# power_block.net
KiCad netlist of a schematic drawn in Altium Designer
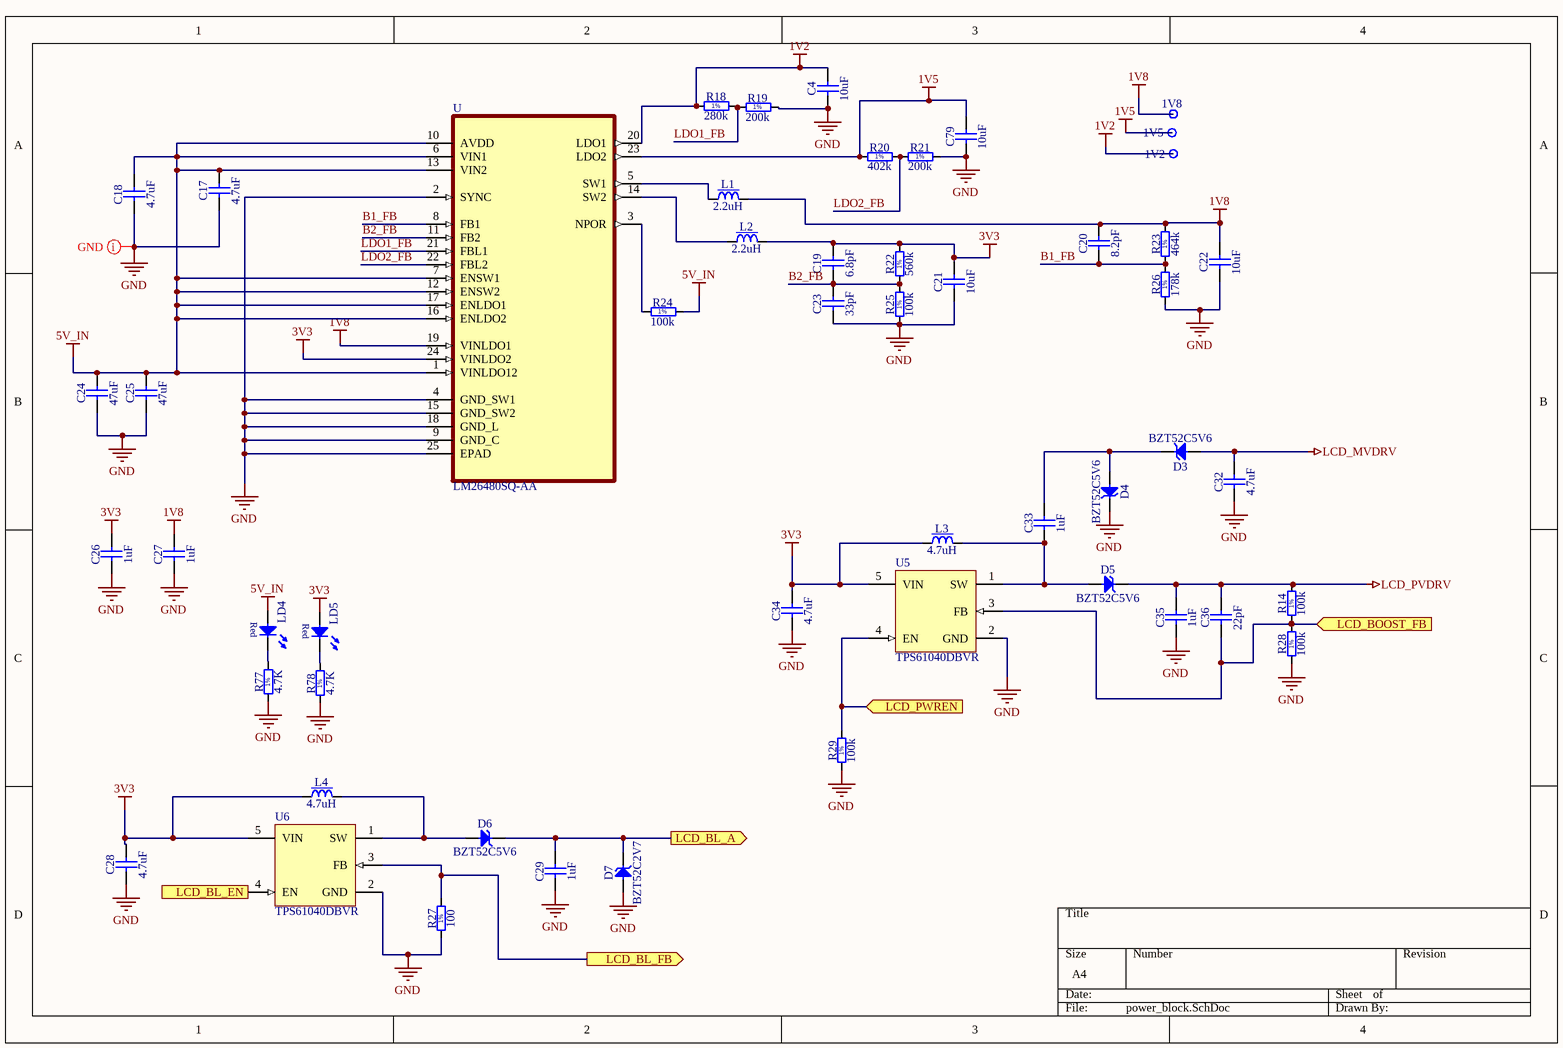
[diagram p0: power_block.SchDoc]

(export (version "E")
  (design (tool "Eeschema 10.0.6"))
  (components
    (comp (ref "1V2")
      (value "Test Point")
      (footprint "TPS127")
      (fields (field (name "PART NUMBER") "SMD_PAD_1.27X1.27MM") (field (name "AUTHOR") "CERN DEM JLC"))
      (libsource (lib "Eletro-mechanical") (part "Test Point"))
    )
    (comp (ref "1V5")
      (value "Test Point")
      (footprint "TPS127")
      (fields (field (name "PART NUMBER") "SMD_PAD_1.27X1.27MM") (field (name "AUTHOR") "CERN DEM JLC"))
      (libsource (lib "Eletro-mechanical") (part "Test Point"))
    )
    (comp (ref "1V8")
      (value "Test Point")
      (footprint "TPS127")
      (fields (field (name "PART NUMBER") "SMD_PAD_1.27X1.27MM") (field (name "AUTHOR") "CERN DEM JLC"))
      (libsource (lib "Eletro-mechanical") (part "Test Point"))
    )
    (comp (ref "C4")
      (value "10uF")
      (footprint "CAPC2013X100N")
      (description "Non-polarised capacitor")
      (fields
        (field (name "PART NUMBER") "CC0805_1.5NF_50V_5%_C0G")
        (field (name "VOLTAGE") "50V")
        (field (name "AUTHOR") "CERN DEM BC")
      )
      (libsource (lib "Capacitors") (part "Capacitor - non polarized"))
    )
    (comp (ref "C17")
      (value "4.7uF")
      (footprint "CAPC2013X100N")
      (description "Non-polarised capacitor")
      (fields
        (field (name "PART NUMBER") "CC0805_1.5NF_50V_5%_C0G")
        (field (name "VOLTAGE") "50V")
        (field (name "AUTHOR") "CERN DEM BC")
      )
      (libsource (lib "Capacitors") (part "Capacitor - non polarized"))
    )
    (comp (ref "C18")
      (value "4.7uF")
      (footprint "CAPC2013X100N")
      (description "Non-polarised capacitor")
      (fields
        (field (name "PART NUMBER") "CC0805_1.5NF_50V_5%_C0G")
        (field (name "VOLTAGE") "50V")
        (field (name "AUTHOR") "CERN DEM BC")
      )
      (libsource (lib "Capacitors") (part "Capacitor - non polarized"))
    )
    (comp (ref "C19")
      (value "6.8pF")
      (footprint "CAPC2013X100N")
      (description "Non-polarised capacitor")
      (fields
        (field (name "PART NUMBER") "CC0805_1.5NF_50V_5%_C0G")
        (field (name "VOLTAGE") "50V")
        (field (name "AUTHOR") "CERN DEM BC")
      )
      (libsource (lib "Capacitors") (part "Capacitor - non polarized"))
    )
    (comp (ref "C20")
      (value "8.2pF")
      (footprint "CAPC2013X100N")
      (description "Non-polarised capacitor")
      (fields
        (field (name "PART NUMBER") "CC0805_1.5NF_50V_5%_C0G")
        (field (name "VOLTAGE") "50V")
        (field (name "AUTHOR") "CERN DEM BC")
      )
      (libsource (lib "Capacitors") (part "Capacitor - non polarized"))
    )
    (comp (ref "C21")
      (value "10uF")
      (footprint "CAPC2013X100N")
      (description "Non-polarised capacitor")
      (fields
        (field (name "PART NUMBER") "CC0805_1.5NF_50V_5%_C0G")
        (field (name "VOLTAGE") "50V")
        (field (name "AUTHOR") "CERN DEM BC")
      )
      (libsource (lib "Capacitors") (part "Capacitor - non polarized"))
    )
    (comp (ref "C22")
      (value "10uF")
      (footprint "CAPC2013X100N")
      (description "Non-polarised capacitor")
      (fields
        (field (name "PART NUMBER") "CC0805_1.5NF_50V_5%_C0G")
        (field (name "VOLTAGE") "50V")
        (field (name "AUTHOR") "CERN DEM BC")
      )
      (libsource (lib "Capacitors") (part "Capacitor - non polarized"))
    )
    (comp (ref "C23")
      (value "33pF")
      (footprint "CAPC2013X100N")
      (description "Non-polarised capacitor")
      (fields
        (field (name "PART NUMBER") "CC0805_1.5NF_50V_5%_C0G")
        (field (name "VOLTAGE") "50V")
        (field (name "AUTHOR") "CERN DEM BC")
      )
      (libsource (lib "Capacitors") (part "Capacitor - non polarized"))
    )
    (comp (ref "C24")
      (value "47uF")
      (footprint "CAPC2013X100N")
      (description "Non-polarised capacitor")
      (fields
        (field (name "PART NUMBER") "CC0805_1.5NF_50V_5%_C0G")
        (field (name "VOLTAGE") "50V")
        (field (name "AUTHOR") "CERN DEM BC")
      )
      (libsource (lib "Capacitors") (part "Capacitor - non polarized"))
    )
    (comp (ref "C25")
      (value "47uF")
      (footprint "CAPC2013X100N")
      (description "Non-polarised capacitor")
      (fields
        (field (name "PART NUMBER") "CC0805_1.5NF_50V_5%_C0G")
        (field (name "VOLTAGE") "50V")
        (field (name "AUTHOR") "CERN DEM BC")
      )
      (libsource (lib "Capacitors") (part "Capacitor - non polarized"))
    )
    (comp (ref "C26")
      (value "1uF")
      (footprint "CAPC2013X100N")
      (description "Non-polarised capacitor")
      (fields
        (field (name "PART NUMBER") "CC0805_1.5NF_50V_5%_C0G")
        (field (name "VOLTAGE") "50V")
        (field (name "AUTHOR") "CERN DEM BC")
      )
      (libsource (lib "Capacitors") (part "Capacitor - non polarized"))
    )
    (comp (ref "C27")
      (value "1uF")
      (footprint "CAPC2013X100N")
      (description "Non-polarised capacitor")
      (fields
        (field (name "PART NUMBER") "CC0805_1.5NF_50V_5%_C0G")
        (field (name "VOLTAGE") "50V")
        (field (name "AUTHOR") "CERN DEM BC")
      )
      (libsource (lib "Capacitors") (part "Capacitor - non polarized"))
    )
    (comp (ref "C28")
      (value "4.7uF")
      (footprint "CAPC2013X100N")
      (description "Non-polarised capacitor")
      (fields
        (field (name "PART NUMBER") "CC0805_1.5NF_50V_5%_C0G")
        (field (name "VOLTAGE") "50V")
        (field (name "AUTHOR") "CERN DEM BC")
      )
      (libsource (lib "Capacitors") (part "Capacitor - non polarized"))
    )
    (comp (ref "C29")
      (value "1uF")
      (footprint "CAPC2013X100N")
      (description "Non-polarised capacitor")
      (fields
        (field (name "PART NUMBER") "CC0805_1.5NF_50V_5%_C0G")
        (field (name "VOLTAGE") "50V")
        (field (name "AUTHOR") "CERN DEM BC")
      )
      (libsource (lib "Capacitors") (part "Capacitor - non polarized"))
    )
    (comp (ref "C32")
      (value "4.7uF")
      (footprint "CAPC2013X100N")
      (description "Non-polarised capacitor")
      (fields
        (field (name "PART NUMBER") "CC0805_1.5NF_50V_5%_C0G")
        (field (name "VOLTAGE") "50V")
        (field (name "AUTHOR") "CERN DEM BC")
      )
      (libsource (lib "Capacitors") (part "Capacitor - non polarized"))
    )
    (comp (ref "C33")
      (value "1uF")
      (footprint "CAPC2013X100N")
      (description "Non-polarised capacitor")
      (fields
        (field (name "PART NUMBER") "CC0805_1.5NF_50V_5%_C0G")
        (field (name "VOLTAGE") "50V")
        (field (name "AUTHOR") "CERN DEM BC")
      )
      (libsource (lib "Capacitors") (part "Capacitor - non polarized"))
    )
    (comp (ref "C34")
      (value "4.7uF")
      (footprint "CAPC2013X100N")
      (description "Non-polarised capacitor")
      (fields
        (field (name "PART NUMBER") "CC0805_1.5NF_50V_5%_C0G")
        (field (name "VOLTAGE") "50V")
        (field (name "AUTHOR") "CERN DEM BC")
      )
      (libsource (lib "Capacitors") (part "Capacitor - non polarized"))
    )
    (comp (ref "C35")
      (value "1uF")
      (footprint "CAPC2013X100N")
      (description "Non-polarised capacitor")
      (fields
        (field (name "PART NUMBER") "CC0805_1.5NF_50V_5%_C0G")
        (field (name "VOLTAGE") "50V")
        (field (name "AUTHOR") "CERN DEM BC")
      )
      (libsource (lib "Capacitors") (part "Capacitor - non polarized"))
    )
    (comp (ref "C36")
      (value "22pF")
      (footprint "CAPC2013X100N")
      (description "Non-polarised capacitor")
      (fields
        (field (name "PART NUMBER") "CC0805_1.5NF_50V_5%_C0G")
        (field (name "VOLTAGE") "50V")
        (field (name "AUTHOR") "CERN DEM BC")
      )
      (libsource (lib "Capacitors") (part "Capacitor - non polarized"))
    )
    (comp (ref "C79")
      (value "10uF")
      (footprint "CAPC2013X100N")
      (description "Non-polarised capacitor")
      (fields
        (field (name "PART NUMBER") "CC0805_1.5NF_50V_5%_C0G")
        (field (name "VOLTAGE") "50V")
        (field (name "AUTHOR") "CERN DEM BC")
      )
      (libsource (lib "Capacitors") (part "Capacitor - non polarized"))
    )
    (comp (ref "D3")
      (value "BZT52C5V6")
      (footprint "SOD3715X145N")
      (description "Zener Diode")
      (fields
        (field (name "VOLTAGE") "5V6")
        (field (name "POWER") "0.5W")
        (field (name "AUTHOR") "CERN DEM JLC")
      )
      (libsource (lib "ICs And Semiconductors") (part "Diode Zener"))
    )
    (comp (ref "D4")
      (value "BZT52C5V6")
      (footprint "SOD3715X145N")
      (description "Zener Diode")
      (fields
        (field (name "VOLTAGE") "5V6")
        (field (name "POWER") "0.5W")
        (field (name "AUTHOR") "CERN DEM JLC")
      )
      (libsource (lib "ICs And Semiconductors") (part "Diode Zener"))
    )
    (comp (ref "D5")
      (value "BZT52C5V6")
      (footprint "SOD3715X145N")
      (description "Zener Diode")
      (fields
        (field (name "VOLTAGE") "5V6")
        (field (name "POWER") "0.5W")
        (field (name "AUTHOR") "CERN DEM JLC")
      )
      (libsource (lib "ICs And Semiconductors") (part "Diode Zener"))
    )
    (comp (ref "D6")
      (value "BZT52C5V6")
      (footprint "SOD3715X145N")
      (description "Zener Diode")
      (fields
        (field (name "VOLTAGE") "5V6")
        (field (name "POWER") "0.5W")
        (field (name "AUTHOR") "CERN DEM JLC")
      )
      (libsource (lib "ICs And Semiconductors") (part "Diode Zener"))
    )
    (comp (ref "D7")
      (value "BZT52C2V7")
      (footprint "SOD3715X145N")
      (description "Zener Diode")
      (fields
        (field (name "VOLTAGE") "2V7")
        (field (name "POWER") "500mW")
        (field (name "AUTHOR") "CERN DEM JLC")
      )
      (libsource (lib "ICs And Semiconductors") (part "Diode Zener"))
    )
    (comp (ref "L1")
      (value "2.2uH")
      (footprint "IND_MURATA-PS_8200")
      (description "Inductor With Core")
      (fields
        (field (name "PART NUMBER") "IND_22UH_10%_MURATA-PS_8200")
        (field (name "POWER") "320mA")
        (field (name "AUTHOR") "CERN DEM JMW")
      )
      (libsource (lib "Inductors & Transformers") (part "Inductor With Magnetic core"))
    )
    (comp (ref "L2")
      (value "2.2uH")
      (footprint "IND_MURATA-PS_8200")
      (description "Inductor With Core")
      (fields
        (field (name "PART NUMBER") "IND_22UH_10%_MURATA-PS_8200")
        (field (name "POWER") "320mA")
        (field (name "AUTHOR") "CERN DEM JMW")
      )
      (libsource (lib "Inductors & Transformers") (part "Inductor With Magnetic core"))
    )
    (comp (ref "L3")
      (value "4.7uH")
      (footprint "IND_MURATA-PS_8200")
      (description "Inductor With Core")
      (fields
        (field (name "PART NUMBER") "IND_22UH_10%_MURATA-PS_8200")
        (field (name "POWER") "320mA")
        (field (name "AUTHOR") "CERN DEM JMW")
      )
      (libsource (lib "Inductors & Transformers") (part "Inductor With Magnetic core"))
    )
    (comp (ref "L4")
      (value "4.7uH")
      (footprint "IND_MURATA-PS_8200")
      (description "Inductor With Core")
      (fields
        (field (name "PART NUMBER") "IND_22UH_10%_MURATA-PS_8200")
        (field (name "POWER") "320mA")
        (field (name "AUTHOR") "CERN DEM JMW")
      )
      (libsource (lib "Inductors & Transformers") (part "Inductor With Magnetic core"))
    )
    (comp (ref "LD4")
      (value "Super Red")
      (footprint "LED_OSRAM_LSR976")
      (description "LED Red 1C 2A")
      (fields
        (field (name "PART NUMBER") "LED_OSRAM_LSR976")
        (field (name "MANUFACTURER") "OSRAM")
        (field (name "AUTHOR") "CERN DEM JLC")
      )
      (libsource (lib "ICs And Semiconductors") (part "LED Red 1C 2A"))
    )
    (comp (ref "LD5")
      (value "Super Red")
      (footprint "LED_OSRAM_LSR976")
      (description "LED Red 1C 2A")
      (fields
        (field (name "PART NUMBER") "LED_OSRAM_LSR976")
        (field (name "MANUFACTURER") "OSRAM")
        (field (name "AUTHOR") "CERN DEM JLC")
      )
      (libsource (lib "ICs And Semiconductors") (part "LED Red 1C 2A"))
    )
    (comp (ref "R14")
      (value "100k")
      (footprint "RESC1608X55N")
      (description "Resistor - 1%")
      (fields
        (field (name "PART NUMBER") "R0603_100K_1%_0.1W_100PPM")
        (field (name "POWER") "0.1W")
        (field (name "AUTHOR") "CERN DEM JLC")
      )
      (libsource (lib "Resistors") (part "Resistor - 1%"))
    )
    (comp (ref "R18")
      (value "280k")
      (footprint "RESC1608X55N")
      (description "Resistor - 1%")
      (fields
        (field (name "PART NUMBER") "R0603_100K_1%_0.1W_100PPM")
        (field (name "POWER") "0.1W")
        (field (name "AUTHOR") "CERN DEM JLC")
      )
      (libsource (lib "Resistors") (part "Resistor - 1%"))
    )
    (comp (ref "R19")
      (value "200k")
      (footprint "RESC1608X55N")
      (description "Resistor - 1%")
      (fields
        (field (name "PART NUMBER") "R0603_100K_1%_0.1W_100PPM")
        (field (name "POWER") "0.1W")
        (field (name "AUTHOR") "CERN DEM JLC")
      )
      (libsource (lib "Resistors") (part "Resistor - 1%"))
    )
    (comp (ref "R20")
      (value "402k")
      (footprint "RESC1608X55N")
      (description "Resistor - 1%")
      (fields
        (field (name "PART NUMBER") "R0603_100K_1%_0.1W_100PPM")
        (field (name "POWER") "0.1W")
        (field (name "AUTHOR") "CERN DEM JLC")
      )
      (libsource (lib "Resistors") (part "Resistor - 1%"))
    )
    (comp (ref "R21")
      (value "200k")
      (footprint "RESC1608X55N")
      (description "Resistor - 1%")
      (fields
        (field (name "PART NUMBER") "R0603_100K_1%_0.1W_100PPM")
        (field (name "POWER") "0.1W")
        (field (name "AUTHOR") "CERN DEM JLC")
      )
      (libsource (lib "Resistors") (part "Resistor - 1%"))
    )
    (comp (ref "R22")
      (value "560k")
      (footprint "RESC1608X55N")
      (description "Resistor - 1%")
      (fields
        (field (name "PART NUMBER") "R0603_100K_1%_0.1W_100PPM")
        (field (name "POWER") "0.1W")
        (field (name "AUTHOR") "CERN DEM JLC")
      )
      (libsource (lib "Resistors") (part "Resistor - 1%"))
    )
    (comp (ref "R23")
      (value "464k")
      (footprint "RESC1608X55N")
      (description "Resistor - 1%")
      (fields
        (field (name "PART NUMBER") "R0603_100K_1%_0.1W_100PPM")
        (field (name "POWER") "0.1W")
        (field (name "AUTHOR") "CERN DEM JLC")
      )
      (libsource (lib "Resistors") (part "Resistor - 1%"))
    )
    (comp (ref "R24")
      (value "100k")
      (footprint "RESC1608X55N")
      (description "Resistor - 1%")
      (fields
        (field (name "PART NUMBER") "R0603_100K_1%_0.1W_100PPM")
        (field (name "POWER") "0.1W")
        (field (name "AUTHOR") "CERN DEM JLC")
      )
      (libsource (lib "Resistors") (part "Resistor - 1%"))
    )
    (comp (ref "R25")
      (value "100k")
      (footprint "RESC1608X55N")
      (description "Resistor - 1%")
      (fields
        (field (name "PART NUMBER") "R0603_100K_1%_0.1W_100PPM")
        (field (name "POWER") "0.1W")
        (field (name "AUTHOR") "CERN DEM JLC")
      )
      (libsource (lib "Resistors") (part "Resistor - 1%"))
    )
    (comp (ref "R26")
      (value "178k")
      (footprint "RESC1608X55N")
      (description "Resistor - 1%")
      (fields
        (field (name "PART NUMBER") "R0603_100K_1%_0.1W_100PPM")
        (field (name "POWER") "0.1W")
        (field (name "AUTHOR") "CERN DEM JLC")
      )
      (libsource (lib "Resistors") (part "Resistor - 1%"))
    )
    (comp (ref "R27")
      (value "100")
      (footprint "RESC1608X55N")
      (description "Resistor - 1%")
      (fields
        (field (name "PART NUMBER") "R0603_100K_1%_0.1W_100PPM")
        (field (name "POWER") "0.1W")
        (field (name "AUTHOR") "CERN DEM JLC")
      )
      (libsource (lib "Resistors") (part "Resistor - 1%"))
    )
    (comp (ref "R28")
      (value "100k")
      (footprint "RESC1608X55N")
      (description "Resistor - 1%")
      (fields
        (field (name "PART NUMBER") "R0603_100K_1%_0.1W_100PPM")
        (field (name "POWER") "0.1W")
        (field (name "AUTHOR") "CERN DEM JLC")
      )
      (libsource (lib "Resistors") (part "Resistor - 1%"))
    )
    (comp (ref "R29")
      (value "100k")
      (footprint "RESC1608X55N")
      (description "Resistor - 1%")
      (fields
        (field (name "PART NUMBER") "R0603_100K_1%_0.1W_100PPM")
        (field (name "POWER") "0.1W")
        (field (name "AUTHOR") "CERN DEM JLC")
      )
      (libsource (lib "Resistors") (part "Resistor - 1%"))
    )
    (comp (ref "R77")
      (value "4.7K")
      (footprint "RESC1608X55N")
      (description "Resistor - 1%")
      (fields
        (field (name "PART NUMBER") "R0603_100K_1%_0.1W_100PPM")
        (field (name "POWER") "0.1W")
        (field (name "AUTHOR") "CERN DEM JLC")
      )
      (libsource (lib "Resistors") (part "Resistor - 1%"))
    )
    (comp (ref "R78")
      (value "4.7K")
      (footprint "RESC1608X55N")
      (description "Resistor - 1%")
      (fields
        (field (name "PART NUMBER") "R0603_100K_1%_0.1W_100PPM")
        (field (name "POWER") "0.1W")
        (field (name "AUTHOR") "CERN DEM JLC")
      )
      (libsource (lib "Resistors") (part "Resistor - 1%"))
    )
    (comp (ref "U")
      (value "LM26480SQ-AA")
      (footprint "QFN400X400X80-25N")
      (fields (field (name "MF") "Texas Instruments"))
      (libsource (lib "LM26480SQ-AA") (part "LM26480SQ-AA"))
    )
    (comp (ref "U5")
      (value "TPS61040DBVR")
      (footprint "TI-DBV5_L")
      (fields (field (name "MANUFACTURER") "Texas Instruments"))
      (libsource (lib "TI Power Management Lighting and Display") (part "TPS61040DBVR"))
    )
    (comp (ref "U6")
      (value "TPS61040DBVR")
      (footprint "TI-DBV5_L")
      (fields (field (name "MANUFACTURER") "Texas Instruments"))
      (libsource (lib "TI Power Management Lighting and Display") (part "TPS61040DBVR"))
    )
  )
  (nets
    (net (code "1") (name "/B1_FB") (class "Default")
      (node (ref "C20") (pin "1") (pinfunction "1_1") (pintype "passive"))
      (node (ref "R23") (pin "1") (pinfunction "1_1") (pintype "passive"))
      (node (ref "R26") (pin "2") (pinfunction "2_2") (pintype "passive"))
      (node (ref "U") (pin "8") (pinfunction "FB1_8") (pintype "input"))
    )
    (net (code "2") (name "/B2_FB") (class "Default")
      (node (ref "C19") (pin "1") (pinfunction "1_1") (pintype "passive"))
      (node (ref "C23") (pin "2") (pinfunction "2_2") (pintype "passive"))
      (node (ref "R22") (pin "1") (pinfunction "1_1") (pintype "passive"))
      (node (ref "R25") (pin "2") (pinfunction "2_2") (pintype "passive"))
      (node (ref "U") (pin "11") (pinfunction "FB2_11") (pintype "input"))
    )
    (net (code "3") (name "/LCD_BL_A") (class "Default")
      (node (ref "C29") (pin "2") (pinfunction "2_2") (pintype "passive"))
      (node (ref "D6") (pin "1") (pinfunction "C_1") (pintype "passive"))
      (node (ref "D7") (pin "1") (pinfunction "C_1") (pintype "passive"))
    )
    (net (code "4") (name "/LCD_BL_EN") (class "Default")
      (node (ref "U6") (pin "4") (pinfunction "EN_4") (pintype "input"))
    )
    (net (code "5") (name "/LCD_BL_FB") (class "Default")
      (node (ref "R27") (pin "2") (pinfunction "2_2") (pintype "passive"))
      (node (ref "U6") (pin "3") (pinfunction "FB_3") (pintype "input"))
    )
    (net (code "6") (name "/LCD_BOOST_FB") (class "Default")
      (node (ref "C36") (pin "1") (pinfunction "1_1") (pintype "passive"))
      (node (ref "R14") (pin "1") (pinfunction "1_1") (pintype "passive"))
      (node (ref "R28") (pin "2") (pinfunction "2_2") (pintype "passive"))
      (node (ref "U5") (pin "3") (pinfunction "FB_3") (pintype "input"))
    )
    (net (code "7") (name "/LCD_PWREN") (class "Default")
      (node (ref "R29") (pin "2") (pinfunction "2_2") (pintype "passive"))
      (node (ref "U5") (pin "4") (pinfunction "EN_4") (pintype "input"))
    )
    (net (code "8") (name "/LDO1_FB") (class "Default")
      (node (ref "R18") (pin "2") (pinfunction "2_2") (pintype "passive"))
      (node (ref "R19") (pin "1") (pinfunction "1_1") (pintype "passive"))
      (node (ref "U") (pin "21") (pinfunction "FBL1_21") (pintype "input"))
    )
    (net (code "9") (name "/LDO2_FB") (class "Default")
      (node (ref "R20") (pin "2") (pinfunction "2_2") (pintype "passive"))
      (node (ref "R21") (pin "1") (pinfunction "1_1") (pintype "passive"))
      (node (ref "U") (pin "22") (pinfunction "FBL2_22") (pintype "input"))
    )
    (net (code "10") (name "1V2") (class "Default")
      (node (ref "1V2") (pin "1") (pinfunction "1_1") (pintype "bidirectional"))
      (node (ref "C4") (pin "2") (pinfunction "2_2") (pintype "passive"))
      (node (ref "R18") (pin "1") (pinfunction "1_1") (pintype "passive"))
      (node (ref "U") (pin "20") (pinfunction "LDO1_20") (pintype "output"))
    )
    (net (code "11") (name "1V5") (class "Default")
      (node (ref "1V5") (pin "1") (pinfunction "1_1") (pintype "bidirectional"))
      (node (ref "C79") (pin "2") (pinfunction "2_2") (pintype "passive"))
      (node (ref "R20") (pin "1") (pinfunction "1_1") (pintype "passive"))
      (node (ref "U") (pin "23") (pinfunction "LDO2_23") (pintype "output"))
    )
    (net (code "12") (name "1V8") (class "Default")
      (node (ref "1V8") (pin "1") (pinfunction "1_1") (pintype "bidirectional"))
      (node (ref "C20") (pin "2") (pinfunction "2_2") (pintype "passive"))
      (node (ref "C22") (pin "2") (pinfunction "2_2") (pintype "passive"))
      (node (ref "C27") (pin "2") (pinfunction "2_2") (pintype "passive"))
      (node (ref "L1") (pin "2") (pinfunction "2_2") (pintype "passive"))
      (node (ref "R23") (pin "2") (pinfunction "2_2") (pintype "passive"))
      (node (ref "U") (pin "19") (pinfunction "VINLDO1_19") (pintype "input"))
    )
    (net (code "13") (name "3V3") (class "Default")
      (node (ref "C19") (pin "2") (pinfunction "2_2") (pintype "passive"))
      (node (ref "C21") (pin "2") (pinfunction "2_2") (pintype "passive"))
      (node (ref "C26") (pin "2") (pinfunction "2_2") (pintype "passive"))
      (node (ref "C28") (pin "2") (pinfunction "2_2") (pintype "passive"))
      (node (ref "C34") (pin "2") (pinfunction "2_2") (pintype "passive"))
      (node (ref "L2") (pin "2") (pinfunction "2_2") (pintype "passive"))
      (node (ref "L3") (pin "1") (pinfunction "1_1") (pintype "passive"))
      (node (ref "L4") (pin "1") (pinfunction "1_1") (pintype "passive"))
      (node (ref "LD5") (pin "2") (pinfunction "A_2") (pintype "passive"))
      (node (ref "R22") (pin "2") (pinfunction "2_2") (pintype "passive"))
      (node (ref "U") (pin "24") (pinfunction "VINLDO2_24") (pintype "input"))
      (node (ref "U5") (pin "5") (pinfunction "VIN_5") (pintype "power_in"))
      (node (ref "U6") (pin "5") (pinfunction "VIN_5") (pintype "power_in"))
    )
    (net (code "14") (name "5V_IN") (class "Default")
      (node (ref "C17") (pin "2") (pinfunction "2_2") (pintype "passive"))
      (node (ref "C18") (pin "2") (pinfunction "2_2") (pintype "passive"))
      (node (ref "C24") (pin "2") (pinfunction "2_2") (pintype "passive"))
      (node (ref "C25") (pin "2") (pinfunction "2_2") (pintype "passive"))
      (node (ref "LD4") (pin "2") (pinfunction "A_2") (pintype "passive"))
      (node (ref "R24") (pin "2") (pinfunction "2_2") (pintype "passive"))
      (node (ref "U") (pin "1") (pinfunction "VINLDO12_1") (pintype "input"))
      (node (ref "U") (pin "10") (pinfunction "AVDD_10") (pintype "power_in"))
      (node (ref "U") (pin "12") (pinfunction "ENSW2_12") (pintype "input"))
      (node (ref "U") (pin "13") (pinfunction "VIN2_13") (pintype "power_in"))
      (node (ref "U") (pin "16") (pinfunction "ENLDO2_16") (pintype "input"))
      (node (ref "U") (pin "17") (pinfunction "ENLDO1_17") (pintype "input"))
      (node (ref "U") (pin "6") (pinfunction "VIN1_6") (pintype "power_in"))
      (node (ref "U") (pin "7") (pinfunction "ENSW1_7") (pintype "input"))
    )
    (net (code "15") (name "GND") (class "Default")
      (node (ref "C17") (pin "1") (pinfunction "1_1") (pintype "passive"))
      (node (ref "C18") (pin "1") (pinfunction "1_1") (pintype "passive"))
      (node (ref "C21") (pin "1") (pinfunction "1_1") (pintype "passive"))
      (node (ref "C22") (pin "1") (pinfunction "1_1") (pintype "passive"))
      (node (ref "C23") (pin "1") (pinfunction "1_1") (pintype "passive"))
      (node (ref "C24") (pin "1") (pinfunction "1_1") (pintype "passive"))
      (node (ref "C25") (pin "1") (pinfunction "1_1") (pintype "passive"))
      (node (ref "C26") (pin "1") (pinfunction "1_1") (pintype "passive"))
      (node (ref "C27") (pin "1") (pinfunction "1_1") (pintype "passive"))
      (node (ref "C28") (pin "1") (pinfunction "1_1") (pintype "passive"))
      (node (ref "C29") (pin "1") (pinfunction "1_1") (pintype "passive"))
      (node (ref "C32") (pin "1") (pinfunction "1_1") (pintype "passive"))
      (node (ref "C34") (pin "1") (pinfunction "1_1") (pintype "passive"))
      (node (ref "C35") (pin "1") (pinfunction "1_1") (pintype "passive"))
      (node (ref "C4") (pin "1") (pinfunction "1_1") (pintype "passive"))
      (node (ref "C79") (pin "1") (pinfunction "1_1") (pintype "passive"))
      (node (ref "D4") (pin "1") (pinfunction "C_1") (pintype "passive"))
      (node (ref "D7") (pin "2") (pinfunction "A_2") (pintype "passive"))
      (node (ref "R19") (pin "2") (pinfunction "2_2") (pintype "passive"))
      (node (ref "R21") (pin "2") (pinfunction "2_2") (pintype "passive"))
      (node (ref "R25") (pin "1") (pinfunction "1_1") (pintype "passive"))
      (node (ref "R26") (pin "1") (pinfunction "1_1") (pintype "passive"))
      (node (ref "R27") (pin "1") (pinfunction "1_1") (pintype "passive"))
      (node (ref "R28") (pin "1") (pinfunction "1_1") (pintype "passive"))
      (node (ref "R29") (pin "1") (pinfunction "1_1") (pintype "passive"))
      (node (ref "R77") (pin "1") (pinfunction "1_1") (pintype "passive"))
      (node (ref "R78") (pin "1") (pinfunction "1_1") (pintype "passive"))
      (node (ref "U") (pin "15") (pinfunction "GND_SW2_15") (pintype "passive"))
      (node (ref "U") (pin "18") (pinfunction "GND_L_18") (pintype "passive"))
      (node (ref "U") (pin "2") (pinfunction "SYNC_2") (pintype "input"))
      (node (ref "U") (pin "25") (pinfunction "EPAD_25") (pintype "passive"))
      (node (ref "U") (pin "4") (pinfunction "GND_SW1_4") (pintype "passive"))
      (node (ref "U") (pin "9") (pinfunction "GND_C_9") (pintype "passive"))
      (node (ref "U5") (pin "2") (pinfunction "GND_2") (pintype "power_in"))
      (node (ref "U6") (pin "2") (pinfunction "GND_2") (pintype "power_in"))
    )
    (net (code "16") (name "LCD_MVDRV") (class "Default")
      (node (ref "C32") (pin "2") (pinfunction "2_2") (pintype "passive"))
      (node (ref "D3") (pin "2") (pinfunction "A_2") (pintype "passive"))
    )
    (net (code "17") (name "LCD_PVDRV") (class "Default")
      (node (ref "C35") (pin "2") (pinfunction "2_2") (pintype "passive"))
      (node (ref "C36") (pin "2") (pinfunction "2_2") (pintype "passive"))
      (node (ref "D5") (pin "1") (pinfunction "C_1") (pintype "passive"))
      (node (ref "R14") (pin "2") (pinfunction "2_2") (pintype "passive"))
    )
    (net (code "18") (name "Net-(D3-C)") (class "Default")
      (node (ref "C33") (pin "2") (pinfunction "2_2") (pintype "passive"))
      (node (ref "D3") (pin "1") (pinfunction "C_1") (pintype "passive"))
      (node (ref "D4") (pin "2") (pinfunction "A_2") (pintype "passive"))
    )
    (net (code "19") (name "Net-(D5-A)") (class "Default")
      (node (ref "C33") (pin "1") (pinfunction "1_1") (pintype "passive"))
      (node (ref "D5") (pin "2") (pinfunction "A_2") (pintype "passive"))
      (node (ref "L3") (pin "2") (pinfunction "2_2") (pintype "passive"))
      (node (ref "U5") (pin "1") (pinfunction "SW_1") (pintype "power_in"))
    )
    (net (code "20") (name "Net-(D6-A)") (class "Default")
      (node (ref "D6") (pin "2") (pinfunction "A_2") (pintype "passive"))
      (node (ref "L4") (pin "2") (pinfunction "2_2") (pintype "passive"))
      (node (ref "U6") (pin "1") (pinfunction "SW_1") (pintype "power_in"))
    )
    (net (code "21") (name "Net-(LD4-C)") (class "Default")
      (node (ref "LD4") (pin "1") (pinfunction "C_1") (pintype "passive"))
      (node (ref "R77") (pin "2") (pinfunction "2_2") (pintype "passive"))
    )
    (net (code "22") (name "Net-(LD5-C)") (class "Default")
      (node (ref "LD5") (pin "1") (pinfunction "C_1") (pintype "passive"))
      (node (ref "R78") (pin "2") (pinfunction "2_2") (pintype "passive"))
    )
    (net (code "23") (name "Net-(U-NPOR)") (class "Default")
      (node (ref "R24") (pin "1") (pinfunction "1_1") (pintype "passive"))
      (node (ref "U") (pin "3") (pinfunction "NPOR_3") (pintype "output"))
    )
    (net (code "24") (name "Net-(U-SW1)") (class "Default")
      (node (ref "L1") (pin "1") (pinfunction "1_1") (pintype "passive"))
      (node (ref "U") (pin "5") (pinfunction "SW1_5") (pintype "output"))
    )
    (net (code "25") (name "Net-(U-SW2)") (class "Default")
      (node (ref "L2") (pin "1") (pinfunction "1_1") (pintype "passive"))
      (node (ref "U") (pin "14") (pinfunction "SW2_14") (pintype "output"))
    )
  )
)
